# Contactors.net
KiCad netlist of a schematic drawn in Altium Designer
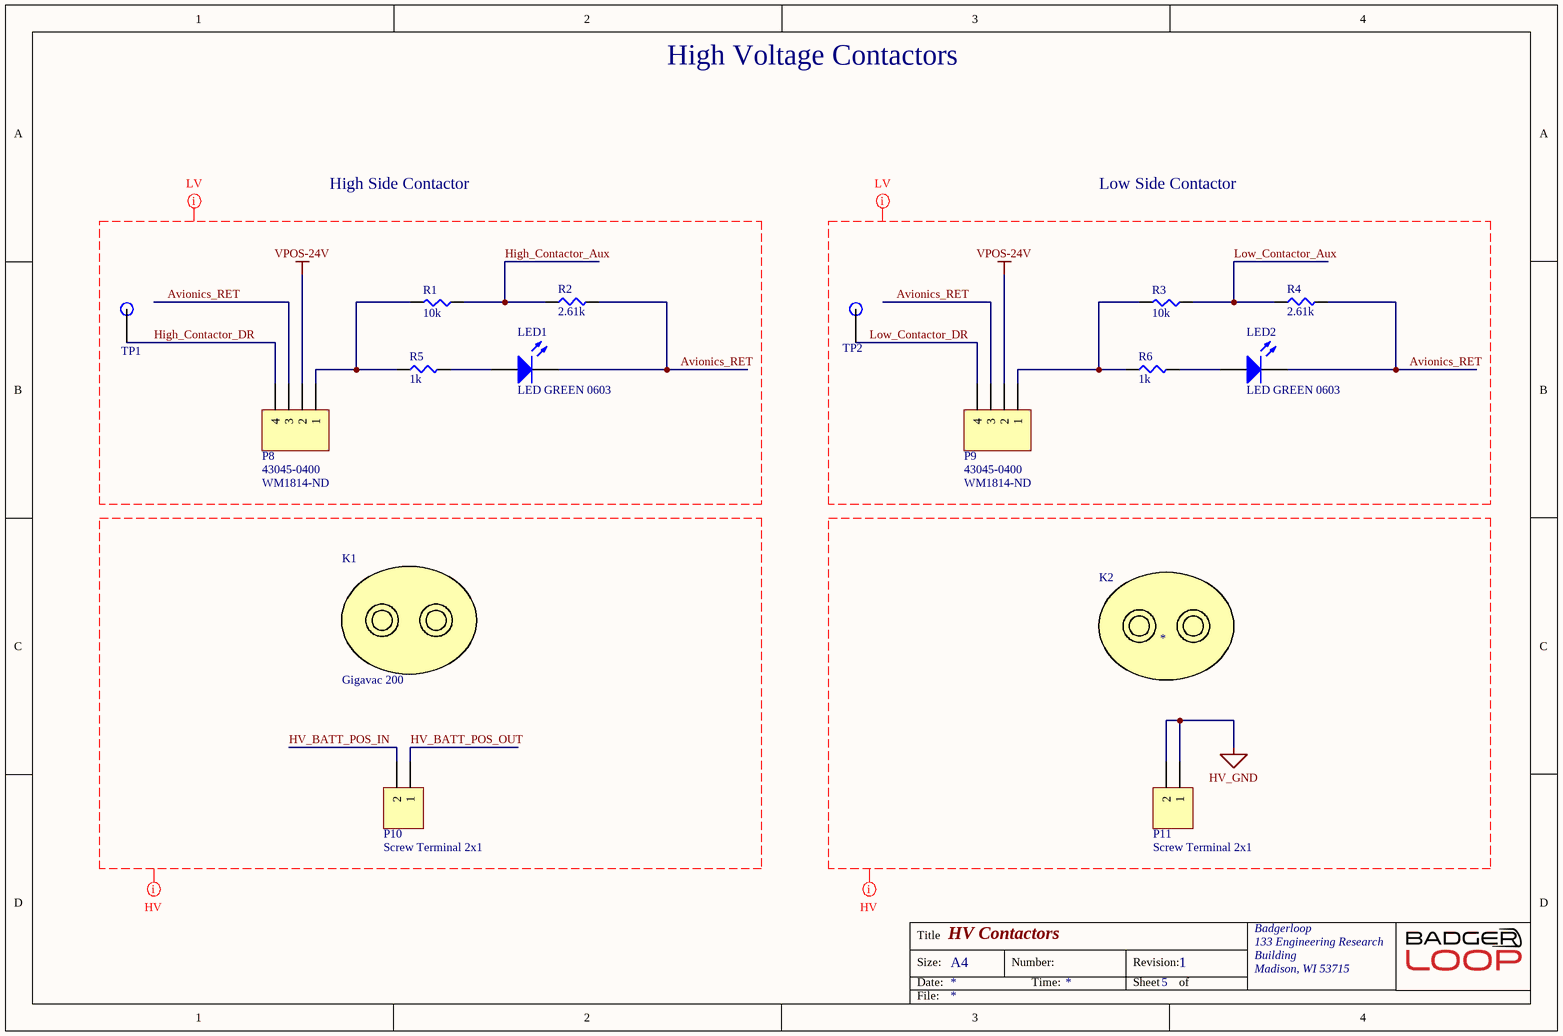
[diagram p0: Contactors.SchDoc]

(export (version "E")
  (design (tool "Eeschema 10.0.6"))
  (components
    (comp (ref "K1")
      (value "Gigavac 200")
      (footprint "Gigavac 200")
      (libsource (lib "misc") (part "Gigavac 200"))
    )
    (comp (ref "K2") (value "*") (footprint "Gigavac 200") (libsource (lib "*") (part "Gigavac 200")))
    (comp (ref "LED1")
      (value "LED GREEN 0603")
      (footprint "LED 0603 GREEN")
      (fields (field (name "MANUFACTURER") "Lite-On Inc."))
      (libsource (lib "misc") (part "LED GREEN 0603"))
    )
    (comp (ref "LED2")
      (value "LED GREEN 0603")
      (footprint "LED 0603 GREEN")
      (fields (field (name "MANUFACTURER") "Lite-On Inc."))
      (libsource (lib "misc") (part "LED GREEN 0603"))
    )
    (comp (ref "P8")
      (value "43045-0400")
      (footprint "430450400")
      (description "Male connector dual row 90° 3 mm Pole no. 2x2 Micro-Fit, 43045-0400, Molex")
      (fields (field (name "MANUFACTURER") "Molex") (field (name "SUPPLIER PART NUMBER 1") "WM1814-ND"))
      (libsource (lib "connector") (part "43045-0400"))
    )
    (comp (ref "P9")
      (value "43045-0400")
      (footprint "430450400")
      (description "Male connector dual row 90° 3 mm Pole no. 2x2 Micro-Fit, 43045-0400, Molex")
      (fields (field (name "MANUFACTURER") "Molex") (field (name "SUPPLIER PART NUMBER 1") "WM1814-ND"))
      (libsource (lib "connector") (part "43045-0400"))
    )
    (comp (ref "P10")
      (value "Screw Terminal 2x1")
      (footprint "2POS TERM BLOCK")
      (description "Screw Terminal, 2-Pin")
      (libsource (lib "connector") (part "Screw Terminal 2x1"))
    )
    (comp (ref "P11")
      (value "Screw Terminal 2x1")
      (footprint "2POS TERM BLOCK")
      (description "Screw Terminal, 2-Pin")
      (libsource (lib "connector") (part "Screw Terminal 2x1"))
    )
    (comp (ref "R1")
      (value "10k")
      (footprint "SMD-0805-RES")
      (description "RES SMD 10K OHM 5% 1/2W 0805")
      (fields (field (name "PART NUMBER") "ERJ-P06J103V") (field (name "DIGI-KEY PART NUMBER") "P10KADCT-ND"))
      (libsource (lib "resistors") (part "ERJ-P06J103V"))
    )
    (comp (ref "R2")
      (value "2.61k")
      (footprint "SMD-1206-RES")
      (description "RES SMD 2.61K OHM 1% 1/4W 1206")
      (fields
        (field (name "PART NUMBER") "ERJ-8ENF2611V")
        (field (name "DIGI-KEY PART NUMBER") "P2.61KFCT-ND")
      )
      (libsource (lib "resistors") (part "ERJ-8ENF2611V"))
    )
    (comp (ref "R3")
      (value "10k")
      (footprint "SMD-0805-RES")
      (description "RES SMD 10K OHM 5% 1/2W 0805")
      (fields (field (name "PART NUMBER") "ERJ-P06J103V") (field (name "DIGI-KEY PART NUMBER") "P10KADCT-ND"))
      (libsource (lib "resistors") (part "ERJ-P06J103V"))
    )
    (comp (ref "R4")
      (value "2.61k")
      (footprint "SMD-1206-RES")
      (description "RES SMD 2.61K OHM 1% 1/4W 1206")
      (fields
        (field (name "PART NUMBER") "ERJ-8ENF2611V")
        (field (name "DIGI-KEY PART NUMBER") "P2.61KFCT-ND")
      )
      (libsource (lib "resistors") (part "ERJ-8ENF2611V"))
    )
    (comp (ref "R5")
      (value "1k")
      (footprint "SMD-0805-RES")
      (description "RES SMD 1K OHM 1% 1/8W 0805")
      (fields
        (field (name "PART NUMBER") "ERJ-6ENF1001V")
        (field (name "DIGI-KEY PART NUMBER") "P1.00KCCT-ND")
      )
      (libsource (lib "resistors") (part "ERJ-6ENF1001V"))
    )
    (comp (ref "R6")
      (value "1k")
      (footprint "SMD-0805-RES")
      (description "RES SMD 1K OHM 1% 1/8W 0805")
      (fields
        (field (name "PART NUMBER") "ERJ-6ENF1001V")
        (field (name "DIGI-KEY PART NUMBER") "P1.00KCCT-ND")
      )
      (libsource (lib "resistors") (part "ERJ-6ENF1001V"))
    )
    (comp (ref "TP1")
      (value "TP")
      (footprint "Test Point")
      (description "SMD TEST POINT")
      (libsource (lib "misc") (part "TP"))
    )
    (comp (ref "TP2")
      (value "TP")
      (footprint "Test Point")
      (description "SMD TEST POINT")
      (libsource (lib "misc") (part "TP"))
    )
  )
  (nets
    (net (code "1") (name "/Avionics_RET") (class "Default")
      (node (ref "LED1") (pin "2") (pinfunction "K_2") (pintype "passive"))
      (node (ref "LED2") (pin "2") (pinfunction "K_2") (pintype "passive"))
      (node (ref "P8") (pin "3") (pinfunction "3_3") (pintype "passive"))
      (node (ref "P9") (pin "3") (pinfunction "3_3") (pintype "passive"))
      (node (ref "R2") (pin "2") (pinfunction "2_2") (pintype "passive"))
      (node (ref "R4") (pin "2") (pinfunction "2_2") (pintype "passive"))
    )
    (net (code "2") (name "/HV_BATT_POS_IN") (class "Default")
      (node (ref "P10") (pin "2") (pinfunction "2_2") (pintype "passive"))
    )
    (net (code "3") (name "/HV_BATT_POS_OUT") (class "Default")
      (node (ref "P10") (pin "1") (pinfunction "1_1") (pintype "passive"))
    )
    (net (code "4") (name "/High_Contactor_Aux") (class "Default")
      (node (ref "R1") (pin "1") (pinfunction "1_1") (pintype "passive"))
      (node (ref "R2") (pin "1") (pinfunction "1_1") (pintype "passive"))
    )
    (net (code "5") (name "/High_Contactor_DR") (class "Default")
      (node (ref "P8") (pin "4") (pinfunction "4_4") (pintype "passive"))
      (node (ref "TP1") (pin "1") (pinfunction "1_1") (pintype "passive"))
    )
    (net (code "6") (name "/Low_Contactor_Aux") (class "Default")
      (node (ref "R3") (pin "1") (pinfunction "1_1") (pintype "passive"))
      (node (ref "R4") (pin "1") (pinfunction "1_1") (pintype "passive"))
    )
    (net (code "7") (name "/Low_Contactor_DR") (class "Default")
      (node (ref "P9") (pin "4") (pinfunction "4_4") (pintype "passive"))
      (node (ref "TP2") (pin "1") (pinfunction "1_1") (pintype "passive"))
    )
    (net (code "8") (name "HV_GND") (class "Default")
      (node (ref "P11") (pin "1") (pinfunction "1_1") (pintype "passive"))
      (node (ref "P11") (pin "2") (pinfunction "2_2") (pintype "passive"))
    )
    (net (code "9") (name "Net-(LED1-A)") (class "Default")
      (node (ref "LED1") (pin "1") (pinfunction "A_1") (pintype "passive"))
      (node (ref "R5") (pin "2") (pinfunction "2_2") (pintype "passive"))
    )
    (net (code "10") (name "Net-(LED2-A)") (class "Default")
      (node (ref "LED2") (pin "1") (pinfunction "A_1") (pintype "passive"))
      (node (ref "R6") (pin "2") (pinfunction "2_2") (pintype "passive"))
    )
    (net (code "11") (name "Net-(P8-Pad1)") (class "Default")
      (node (ref "P8") (pin "1") (pinfunction "1_1") (pintype "passive"))
      (node (ref "R1") (pin "2") (pinfunction "2_2") (pintype "passive"))
      (node (ref "R5") (pin "1") (pinfunction "1_1") (pintype "passive"))
    )
    (net (code "12") (name "Net-(P9-Pad1)") (class "Default")
      (node (ref "P9") (pin "1") (pinfunction "1_1") (pintype "passive"))
      (node (ref "R3") (pin "2") (pinfunction "2_2") (pintype "passive"))
      (node (ref "R6") (pin "1") (pinfunction "1_1") (pintype "passive"))
    )
    (net (code "13") (name "VPOS-24V") (class "Default")
      (node (ref "P8") (pin "2") (pinfunction "2_2") (pintype "passive"))
      (node (ref "P9") (pin "2") (pinfunction "2_2") (pintype "passive"))
    )
  )
)
